# SCH_Rubik_2_2024-01-29.net
KiCad netlist of a schematic drawn in EasyEDA
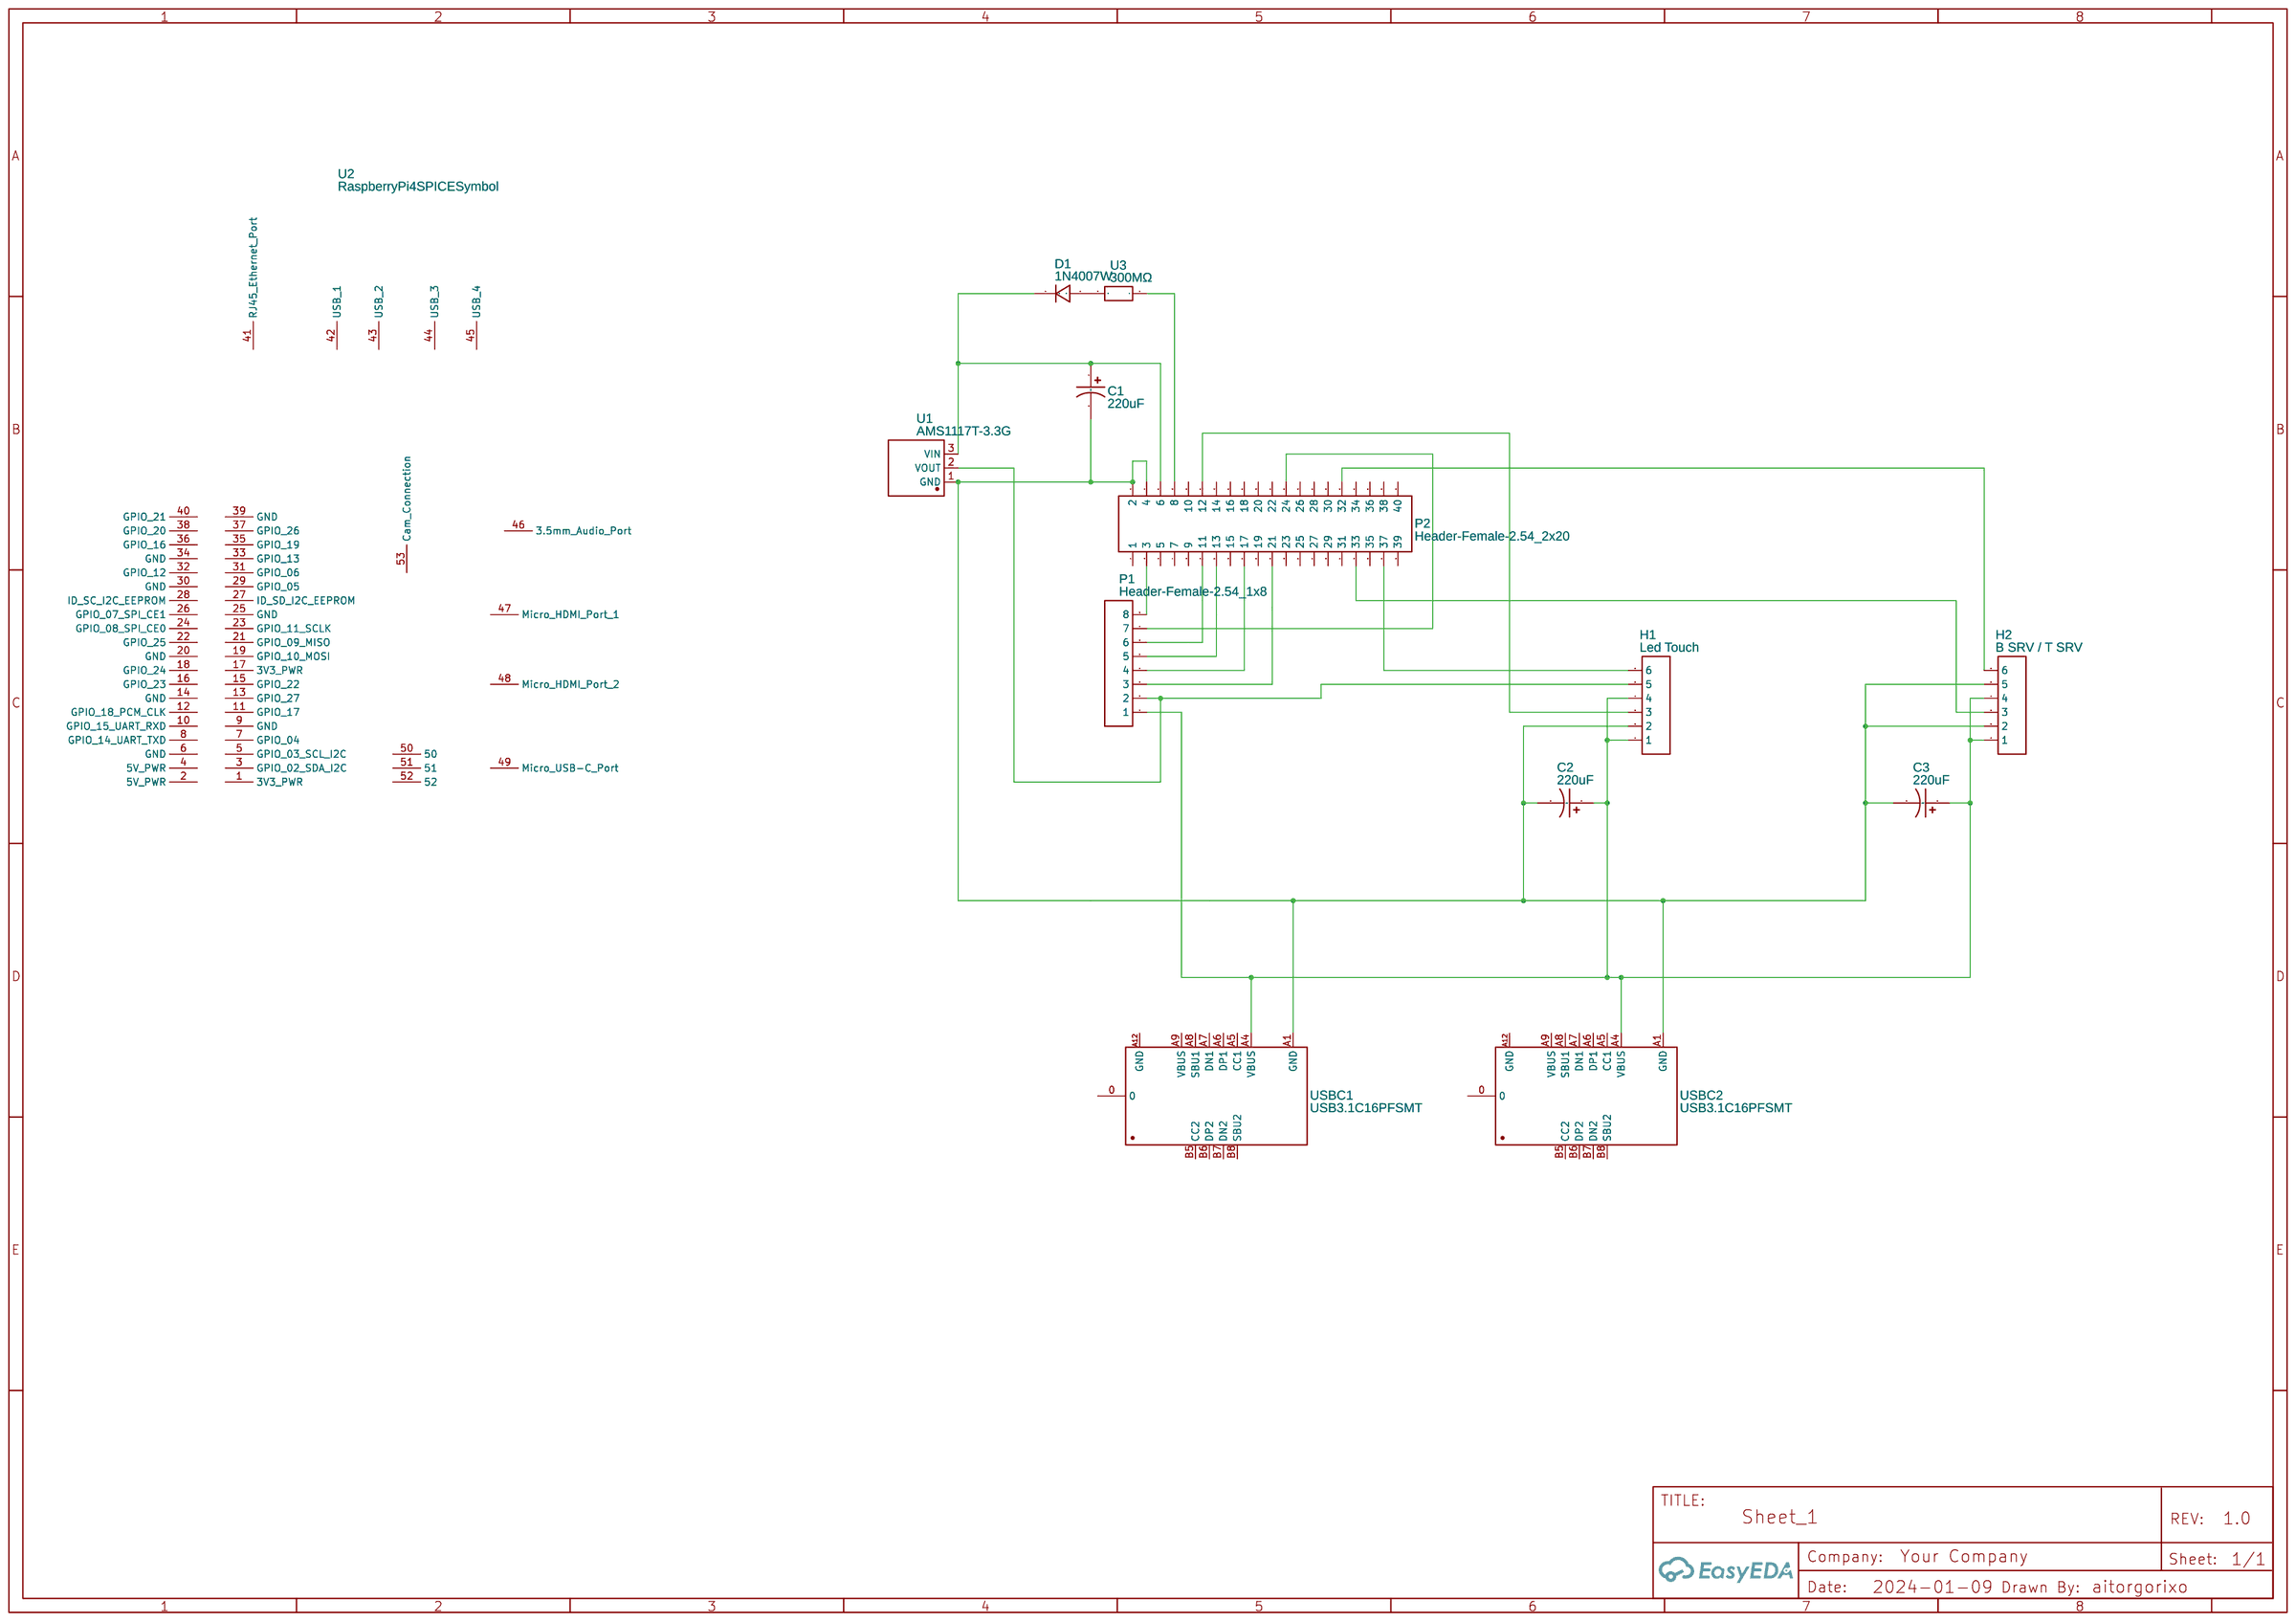
[diagram p0: schematic sheet]

(export (version "E")
  (design (tool "Eeschema 10.0.6"))
  (components
    (comp (ref "C1")
      (value "220uF")
      (fields
        (field (name "Manufacturer Part") "35YXG220MLLCT78X16")
        (field (name "Manufacturer") "rubycon(红宝石)")
      )
      (libsource (lib "") (part "35YXG220MLLCT78X16_1"))
    )
    (comp (ref "C2")
      (value "220uF")
      (fields
        (field (name "Manufacturer Part") "35YXG220MLLCT78X16")
        (field (name "Manufacturer") "rubycon(红宝石)")
      )
      (libsource (lib "") (part "35YXG220MLLCT78X16"))
    )
    (comp (ref "C3")
      (value "220uF")
      (fields
        (field (name "Manufacturer Part") "35YXG220MLLCT78X16")
        (field (name "Manufacturer") "rubycon(红宝石)")
      )
      (libsource (lib "") (part "35YXG220MLLCT78X16"))
    )
    (comp (ref "D1")
      (value "1N4007W")
      (fields (field (name "Manufacturer") "BLUE ROCKET"))
      (libsource (lib "") (part "1N4007W"))
    )
    (comp (ref "H1")
      (value "Led Touch")
      (fields (field (name "Manufacturer Part") "2.54-1x6P直针") (field (name "Manufacturer") "BOOMELE(博穆精密)"))
      (libsource (lib "") (part "Header-Male-2.54_1x6"))
    )
    (comp (ref "H2")
      (value "B SRV / T SRV")
      (fields (field (name "Manufacturer Part") "2.54-1x6P直针") (field (name "Manufacturer") "BOOMELE(博穆精密)"))
      (libsource (lib "") (part "Header-Male-2.54_1x6"))
    )
    (comp (ref "P1")
      (value "Header-Female-2.54_1x8")
      (fields (field (name "Manufacturer Part") "2.54-1*8P母环保") (field (name "Manufacturer") "BOOMELE(博穆精密)"))
      (libsource (lib "") (part "Header-Female-2.54_1x8"))
    )
    (comp (ref "P2")
      (value "Header-Female-2.54_2x20")
      (fields (field (name "Manufacturer Part") "2.54-2*20P母") (field (name "Manufacturer") "BOOMELE(博穆精密)"))
      (libsource (lib "") (part "Header-Female-2.54_2x20"))
    )
    (comp (ref "U1")
      (value "AMS1117T-3.3G")
      (fields (field (name "Manufacturer") "HGC(深圳汉芯)"))
      (libsource (lib "") (part "AMS1117T-3.3G"))
    )
    (comp (ref "U2") (value "RaspberryPi4SPICESymbol") (libsource (lib "") (part "RaspberryPi4SPICESymbol")))
    (comp (ref "U3")
      (value "300MΩ")
      (fields
        (field (name "Manufacturer Part") "WW12JTR300")
        (field (name "Manufacturer") "SEI(Stackpole Electronics Inc.)")
      )
      (libsource (lib "") (part "WW12JTR300"))
    )
    (comp (ref "USBC1")
      (value "USB3.1C16PFSMT")
      (fields (field (name "Manufacturer Part") "918-418K2023S40001") (field (name "Manufacturer") "精拓金"))
      (libsource (lib "") (part "USB3.1C16PFSMT"))
    )
    (comp (ref "USBC2")
      (value "USB3.1C16PFSMT")
      (fields (field (name "Manufacturer Part") "918-418K2023S40001") (field (name "Manufacturer") "精拓金"))
      (libsource (lib "") (part "USB3.1C16PFSMT"))
    )
  )
  (nets
    (net (code "1") (name "Net-(C2-Pad1)") (class "Default")
      (node (ref "C2") (pin "1") (pinfunction "1_1") (pintype "unspecified"))
      (node (ref "C3") (pin "1") (pinfunction "1_1") (pintype "unspecified"))
      (node (ref "H1") (pin "1") (pinfunction "1_1") (pintype "input"))
      (node (ref "H1") (pin "4") (pinfunction "4_4") (pintype "input"))
      (node (ref "H2") (pin "1") (pinfunction "1_1") (pintype "input"))
      (node (ref "H2") (pin "4") (pinfunction "4_4") (pintype "input"))
      (node (ref "P1") (pin "1") (pinfunction "1_1") (pintype "input"))
      (node (ref "USBC1") (pin "A4") (pinfunction "VBUS_A4") (pintype "unspecified"))
      (node (ref "USBC2") (pin "A4") (pinfunction "VBUS_A4") (pintype "unspecified"))
    )
    (net (code "2") (name "Net-(D1-Pad2)") (class "Default")
      (node (ref "D1") (pin "2") (pinfunction "2_2") (pintype "unspecified"))
      (node (ref "U3") (pin "2") (pinfunction "2_2") (pintype "unspecified"))
    )
    (net (code "3") (name "Net-(H1-Pad3)") (class "Default")
      (node (ref "H1") (pin "3") (pinfunction "3_3") (pintype "input"))
      (node (ref "P2") (pin "12") (pinfunction "12_12") (pintype "input"))
    )
    (net (code "4") (name "Net-(H1-Pad6)") (class "Default")
      (node (ref "H1") (pin "6") (pinfunction "6_6") (pintype "input"))
      (node (ref "P2") (pin "37") (pinfunction "37_37") (pintype "input"))
    )
    (net (code "5") (name "Net-(H2-Pad3)") (class "Default")
      (node (ref "H2") (pin "3") (pinfunction "3_3") (pintype "input"))
      (node (ref "P2") (pin "33") (pinfunction "33_33") (pintype "input"))
    )
    (net (code "6") (name "Net-(H2-Pad6)") (class "Default")
      (node (ref "H2") (pin "6") (pinfunction "6_6") (pintype "input"))
      (node (ref "P2") (pin "32") (pinfunction "32_32") (pintype "input"))
    )
    (net (code "7") (name "Net-(P1-Pad3)") (class "Default")
      (node (ref "P1") (pin "3") (pinfunction "3_3") (pintype "input"))
      (node (ref "P2") (pin "21") (pinfunction "21_21") (pintype "input"))
    )
    (net (code "8") (name "Net-(P1-Pad4)") (class "Default")
      (node (ref "P1") (pin "4") (pinfunction "4_4") (pintype "input"))
      (node (ref "P2") (pin "17") (pinfunction "17_17") (pintype "input"))
    )
    (net (code "9") (name "Net-(P1-Pad5)") (class "Default")
      (node (ref "P1") (pin "5") (pinfunction "5_5") (pintype "input"))
      (node (ref "P2") (pin "13") (pinfunction "13_13") (pintype "input"))
    )
    (net (code "10") (name "Net-(P1-Pad6)") (class "Default")
      (node (ref "P1") (pin "6") (pinfunction "6_6") (pintype "input"))
      (node (ref "P2") (pin "11") (pinfunction "11_11") (pintype "input"))
    )
    (net (code "11") (name "Net-(P1-Pad7)") (class "Default")
      (node (ref "P1") (pin "7") (pinfunction "7_7") (pintype "input"))
      (node (ref "P2") (pin "24") (pinfunction "24_24") (pintype "input"))
    )
    (net (code "12") (name "Net-(P1-Pad8)") (class "Default")
      (node (ref "P1") (pin "8") (pinfunction "8_8") (pintype "input"))
      (node (ref "P2") (pin "3") (pinfunction "3_3") (pintype "input"))
    )
    (net (code "13") (name "Net-(P2-Pad8)") (class "Default")
      (node (ref "P2") (pin "8") (pinfunction "8_8") (pintype "input"))
      (node (ref "U3") (pin "1") (pinfunction "1_1") (pintype "unspecified"))
    )
    (net (code "14") (name "Net-(U1-GND)") (class "Default")
      (node (ref "C1") (pin "2") (pinfunction "2_2") (pintype "unspecified"))
      (node (ref "C2") (pin "2") (pinfunction "2_2") (pintype "unspecified"))
      (node (ref "C3") (pin "2") (pinfunction "2_2") (pintype "unspecified"))
      (node (ref "H1") (pin "2") (pinfunction "2_2") (pintype "input"))
      (node (ref "H2") (pin "2") (pinfunction "2_2") (pintype "input"))
      (node (ref "H2") (pin "5") (pinfunction "5_5") (pintype "input"))
      (node (ref "P2") (pin "2") (pinfunction "2_2") (pintype "input"))
      (node (ref "P2") (pin "4") (pinfunction "4_4") (pintype "input"))
      (node (ref "U1") (pin "1") (pinfunction "GND_1") (pintype "unspecified"))
      (node (ref "USBC1") (pin "A1") (pinfunction "GND_A1") (pintype "unspecified"))
      (node (ref "USBC2") (pin "A1") (pinfunction "GND_A1") (pintype "unspecified"))
    )
    (net (code "15") (name "Net-(U1-VIN)") (class "Default")
      (node (ref "C1") (pin "1") (pinfunction "1_1") (pintype "unspecified"))
      (node (ref "D1") (pin "1") (pinfunction "1_1") (pintype "unspecified"))
      (node (ref "P2") (pin "6") (pinfunction "6_6") (pintype "input"))
      (node (ref "U1") (pin "3") (pinfunction "VIN_3") (pintype "unspecified"))
    )
    (net (code "16") (name "Net-(U1-VOUT)") (class "Default")
      (node (ref "H1") (pin "5") (pinfunction "5_5") (pintype "input"))
      (node (ref "P1") (pin "2") (pinfunction "2_2") (pintype "input"))
      (node (ref "U1") (pin "2") (pinfunction "VOUT_2") (pintype "unspecified"))
    )
    (net (code "17") (name "unconnected-(P2-Pad1)") (class "Default")
      (node (ref "P2") (pin "1") (pinfunction "1_1") (pintype "input"))
    )
    (net (code "18") (name "unconnected-(P2-Pad5)") (class "Default")
      (node (ref "P2") (pin "5") (pinfunction "5_5") (pintype "input"))
    )
    (net (code "19") (name "unconnected-(P2-Pad7)") (class "Default")
      (node (ref "P2") (pin "7") (pinfunction "7_7") (pintype "input"))
    )
    (net (code "20") (name "unconnected-(P2-Pad9)") (class "Default")
      (node (ref "P2") (pin "9") (pinfunction "9_9") (pintype "input"))
    )
    (net (code "21") (name "unconnected-(P2-Pad10)") (class "Default")
      (node (ref "P2") (pin "10") (pinfunction "10_10") (pintype "input"))
    )
    (net (code "22") (name "unconnected-(P2-Pad14)") (class "Default")
      (node (ref "P2") (pin "14") (pinfunction "14_14") (pintype "input"))
    )
    (net (code "23") (name "unconnected-(P2-Pad15)") (class "Default")
      (node (ref "P2") (pin "15") (pinfunction "15_15") (pintype "input"))
    )
    (net (code "24") (name "unconnected-(P2-Pad16)") (class "Default")
      (node (ref "P2") (pin "16") (pinfunction "16_16") (pintype "input"))
    )
    (net (code "25") (name "unconnected-(P2-Pad18)") (class "Default")
      (node (ref "P2") (pin "18") (pinfunction "18_18") (pintype "input"))
    )
    (net (code "26") (name "unconnected-(P2-Pad19)") (class "Default")
      (node (ref "P2") (pin "19") (pinfunction "19_19") (pintype "input"))
    )
    (net (code "27") (name "unconnected-(P2-Pad20)") (class "Default")
      (node (ref "P2") (pin "20") (pinfunction "20_20") (pintype "input"))
    )
    (net (code "28") (name "unconnected-(P2-Pad22)") (class "Default")
      (node (ref "P2") (pin "22") (pinfunction "22_22") (pintype "input"))
    )
    (net (code "29") (name "unconnected-(P2-Pad23)") (class "Default")
      (node (ref "P2") (pin "23") (pinfunction "23_23") (pintype "input"))
    )
    (net (code "30") (name "unconnected-(P2-Pad25)") (class "Default")
      (node (ref "P2") (pin "25") (pinfunction "25_25") (pintype "input"))
    )
    (net (code "31") (name "unconnected-(P2-Pad26)") (class "Default")
      (node (ref "P2") (pin "26") (pinfunction "26_26") (pintype "input"))
    )
    (net (code "32") (name "unconnected-(P2-Pad27)") (class "Default")
      (node (ref "P2") (pin "27") (pinfunction "27_27") (pintype "input"))
    )
    (net (code "33") (name "unconnected-(P2-Pad28)") (class "Default")
      (node (ref "P2") (pin "28") (pinfunction "28_28") (pintype "input"))
    )
    (net (code "34") (name "unconnected-(P2-Pad29)") (class "Default")
      (node (ref "P2") (pin "29") (pinfunction "29_29") (pintype "input"))
    )
    (net (code "35") (name "unconnected-(P2-Pad30)") (class "Default")
      (node (ref "P2") (pin "30") (pinfunction "30_30") (pintype "input"))
    )
    (net (code "36") (name "unconnected-(P2-Pad31)") (class "Default")
      (node (ref "P2") (pin "31") (pinfunction "31_31") (pintype "input"))
    )
    (net (code "37") (name "unconnected-(P2-Pad34)") (class "Default")
      (node (ref "P2") (pin "34") (pinfunction "34_34") (pintype "input"))
    )
    (net (code "38") (name "unconnected-(P2-Pad35)") (class "Default")
      (node (ref "P2") (pin "35") (pinfunction "35_35") (pintype "input"))
    )
    (net (code "39") (name "unconnected-(P2-Pad36)") (class "Default")
      (node (ref "P2") (pin "36") (pinfunction "36_36") (pintype "input"))
    )
    (net (code "40") (name "unconnected-(P2-Pad38)") (class "Default")
      (node (ref "P2") (pin "38") (pinfunction "38_38") (pintype "input"))
    )
    (net (code "41") (name "unconnected-(P2-Pad39)") (class "Default")
      (node (ref "P2") (pin "39") (pinfunction "39_39") (pintype "input"))
    )
    (net (code "42") (name "unconnected-(P2-Pad40)") (class "Default")
      (node (ref "P2") (pin "40") (pinfunction "40_40") (pintype "input"))
    )
    (net (code "43") (name "unconnected-(U2-3.5mm_Audio_Port-Pad46)") (class "Default")
      (node (ref "U2") (pin "46") (pinfunction "3.5mm_Audio_Port_46") (pintype "unspecified"))
    )
    (net (code "44") (name "unconnected-(U2-3V3_PWR-Pad1)") (class "Default")
      (node (ref "U2") (pin "1") (pinfunction "3V3_PWR_1") (pintype "unspecified"))
    )
    (net (code "45") (name "unconnected-(U2-3V3_PWR-Pad17)") (class "Default")
      (node (ref "U2") (pin "17") (pinfunction "3V3_PWR_17") (pintype "unspecified"))
    )
    (net (code "46") (name "unconnected-(U2-5V_PWR-Pad2)") (class "Default")
      (node (ref "U2") (pin "2") (pinfunction "5V_PWR_2") (pintype "unspecified"))
    )
    (net (code "47") (name "unconnected-(U2-5V_PWR-Pad4)") (class "Default")
      (node (ref "U2") (pin "4") (pinfunction "5V_PWR_4") (pintype "unspecified"))
    )
    (net (code "48") (name "unconnected-(U2-Cam_Connection-Pad53)") (class "Default")
      (node (ref "U2") (pin "53") (pinfunction "Cam_Connection_53") (pintype "unspecified"))
    )
    (net (code "49") (name "unconnected-(U2-GND-Pad6)") (class "Default")
      (node (ref "U2") (pin "6") (pinfunction "GND_6") (pintype "unspecified"))
    )
    (net (code "50") (name "unconnected-(U2-GND-Pad9)") (class "Default")
      (node (ref "U2") (pin "9") (pinfunction "GND_9") (pintype "unspecified"))
    )
    (net (code "51") (name "unconnected-(U2-GND-Pad14)") (class "Default")
      (node (ref "U2") (pin "14") (pinfunction "GND_14") (pintype "unspecified"))
    )
    (net (code "52") (name "unconnected-(U2-GND-Pad20)") (class "Default")
      (node (ref "U2") (pin "20") (pinfunction "GND_20") (pintype "unspecified"))
    )
    (net (code "53") (name "unconnected-(U2-GND-Pad25)") (class "Default")
      (node (ref "U2") (pin "25") (pinfunction "GND_25") (pintype "unspecified"))
    )
    (net (code "54") (name "unconnected-(U2-GND-Pad30)") (class "Default")
      (node (ref "U2") (pin "30") (pinfunction "GND_30") (pintype "unspecified"))
    )
    (net (code "55") (name "unconnected-(U2-GND-Pad34)") (class "Default")
      (node (ref "U2") (pin "34") (pinfunction "GND_34") (pintype "unspecified"))
    )
    (net (code "56") (name "unconnected-(U2-GND-Pad39)") (class "Default")
      (node (ref "U2") (pin "39") (pinfunction "GND_39") (pintype "unspecified"))
    )
    (net (code "57") (name "unconnected-(U2-GPIO_02_SDA_I2C-Pad3)") (class "Default")
      (node (ref "U2") (pin "3") (pinfunction "GPIO_02_SDA_I2C_3") (pintype "unspecified"))
    )
    (net (code "58") (name "unconnected-(U2-GPIO_03_SCL_I2C-Pad5)") (class "Default")
      (node (ref "U2") (pin "5") (pinfunction "GPIO_03_SCL_I2C_5") (pintype "unspecified"))
    )
    (net (code "59") (name "unconnected-(U2-GPIO_04-Pad7)") (class "Default")
      (node (ref "U2") (pin "7") (pinfunction "GPIO_04_7") (pintype "unspecified"))
    )
    (net (code "60") (name "unconnected-(U2-GPIO_05-Pad29)") (class "Default")
      (node (ref "U2") (pin "29") (pinfunction "GPIO_05_29") (pintype "unspecified"))
    )
    (net (code "61") (name "unconnected-(U2-GPIO_06-Pad31)") (class "Default")
      (node (ref "U2") (pin "31") (pinfunction "GPIO_06_31") (pintype "unspecified"))
    )
    (net (code "62") (name "unconnected-(U2-GPIO_07_SPI_CE1-Pad26)") (class "Default")
      (node (ref "U2") (pin "26") (pinfunction "GPIO_07_SPI_CE1_26") (pintype "unspecified"))
    )
    (net (code "63") (name "unconnected-(U2-GPIO_08_SPI_CE0-Pad24)") (class "Default")
      (node (ref "U2") (pin "24") (pinfunction "GPIO_08_SPI_CE0_24") (pintype "unspecified"))
    )
    (net (code "64") (name "unconnected-(U2-GPIO_09_MISO-Pad21)") (class "Default")
      (node (ref "U2") (pin "21") (pinfunction "GPIO_09_MISO_21") (pintype "unspecified"))
    )
    (net (code "65") (name "unconnected-(U2-GPIO_10_MOSI-Pad19)") (class "Default")
      (node (ref "U2") (pin "19") (pinfunction "GPIO_10_MOSI_19") (pintype "unspecified"))
    )
    (net (code "66") (name "unconnected-(U2-GPIO_11_SCLK-Pad23)") (class "Default")
      (node (ref "U2") (pin "23") (pinfunction "GPIO_11_SCLK_23") (pintype "unspecified"))
    )
    (net (code "67") (name "unconnected-(U2-GPIO_12-Pad32)") (class "Default")
      (node (ref "U2") (pin "32") (pinfunction "GPIO_12_32") (pintype "unspecified"))
    )
    (net (code "68") (name "unconnected-(U2-GPIO_13-Pad33)") (class "Default")
      (node (ref "U2") (pin "33") (pinfunction "GPIO_13_33") (pintype "unspecified"))
    )
    (net (code "69") (name "unconnected-(U2-GPIO_14_UART_TXD-Pad8)") (class "Default")
      (node (ref "U2") (pin "8") (pinfunction "GPIO_14_UART_TXD_8") (pintype "unspecified"))
    )
    (net (code "70") (name "unconnected-(U2-GPIO_15_UART_RXD-Pad10)") (class "Default")
      (node (ref "U2") (pin "10") (pinfunction "GPIO_15_UART_RXD_10") (pintype "unspecified"))
    )
    (net (code "71") (name "unconnected-(U2-GPIO_16-Pad36)") (class "Default")
      (node (ref "U2") (pin "36") (pinfunction "GPIO_16_36") (pintype "unspecified"))
    )
    (net (code "72") (name "unconnected-(U2-GPIO_17-Pad11)") (class "Default")
      (node (ref "U2") (pin "11") (pinfunction "GPIO_17_11") (pintype "unspecified"))
    )
    (net (code "73") (name "unconnected-(U2-GPIO_18_PCM_CLK-Pad12)") (class "Default")
      (node (ref "U2") (pin "12") (pinfunction "GPIO_18_PCM_CLK_12") (pintype "unspecified"))
    )
    (net (code "74") (name "unconnected-(U2-GPIO_19-Pad35)") (class "Default")
      (node (ref "U2") (pin "35") (pinfunction "GPIO_19_35") (pintype "unspecified"))
    )
    (net (code "75") (name "unconnected-(U2-GPIO_20-Pad38)") (class "Default")
      (node (ref "U2") (pin "38") (pinfunction "GPIO_20_38") (pintype "unspecified"))
    )
    (net (code "76") (name "unconnected-(U2-GPIO_21-Pad40)") (class "Default")
      (node (ref "U2") (pin "40") (pinfunction "GPIO_21_40") (pintype "unspecified"))
    )
    (net (code "77") (name "unconnected-(U2-GPIO_22-Pad15)") (class "Default")
      (node (ref "U2") (pin "15") (pinfunction "GPIO_22_15") (pintype "unspecified"))
    )
    (net (code "78") (name "unconnected-(U2-GPIO_23-Pad16)") (class "Default")
      (node (ref "U2") (pin "16") (pinfunction "GPIO_23_16") (pintype "unspecified"))
    )
    (net (code "79") (name "unconnected-(U2-GPIO_24-Pad18)") (class "Default")
      (node (ref "U2") (pin "18") (pinfunction "GPIO_24_18") (pintype "unspecified"))
    )
    (net (code "80") (name "unconnected-(U2-GPIO_25-Pad22)") (class "Default")
      (node (ref "U2") (pin "22") (pinfunction "GPIO_25_22") (pintype "unspecified"))
    )
    (net (code "81") (name "unconnected-(U2-GPIO_26-Pad37)") (class "Default")
      (node (ref "U2") (pin "37") (pinfunction "GPIO_26_37") (pintype "unspecified"))
    )
    (net (code "82") (name "unconnected-(U2-GPIO_27-Pad13)") (class "Default")
      (node (ref "U2") (pin "13") (pinfunction "GPIO_27_13") (pintype "unspecified"))
    )
    (net (code "83") (name "unconnected-(U2-ID_SC_I2C_EEPROM-Pad28)") (class "Default")
      (node (ref "U2") (pin "28") (pinfunction "ID_SC_I2C_EEPROM_28") (pintype "unspecified"))
    )
    (net (code "84") (name "unconnected-(U2-ID_SD_I2C_EEPROM-Pad27)") (class "Default")
      (node (ref "U2") (pin "27") (pinfunction "ID_SD_I2C_EEPROM_27") (pintype "unspecified"))
    )
    (net (code "85") (name "unconnected-(U2-Micro_HDMI_Port_1-Pad47)") (class "Default")
      (node (ref "U2") (pin "47") (pinfunction "Micro_HDMI_Port_1_47") (pintype "unspecified"))
    )
    (net (code "86") (name "unconnected-(U2-Micro_HDMI_Port_2-Pad48)") (class "Default")
      (node (ref "U2") (pin "48") (pinfunction "Micro_HDMI_Port_2_48") (pintype "unspecified"))
    )
    (net (code "87") (name "unconnected-(U2-Micro_USB-C_Port-Pad49)") (class "Default")
      (node (ref "U2") (pin "49") (pinfunction "Micro_USB-C_Port_49") (pintype "unspecified"))
    )
    (net (code "88") (name "unconnected-(U2-Pad50)") (class "Default")
      (node (ref "U2") (pin "50") (pinfunction "50_50") (pintype "unspecified"))
    )
    (net (code "89") (name "unconnected-(U2-Pad51)") (class "Default")
      (node (ref "U2") (pin "51") (pinfunction "51_51") (pintype "unspecified"))
    )
    (net (code "90") (name "unconnected-(U2-Pad52)") (class "Default")
      (node (ref "U2") (pin "52") (pinfunction "52_52") (pintype "unspecified"))
    )
    (net (code "91") (name "unconnected-(U2-RJ45_Ethernet_Port-Pad41)") (class "Default")
      (node (ref "U2") (pin "41") (pinfunction "RJ45_Ethernet_Port_41") (pintype "unspecified"))
    )
    (net (code "92") (name "unconnected-(U2-USB_1-Pad42)") (class "Default")
      (node (ref "U2") (pin "42") (pinfunction "USB_1_42") (pintype "unspecified"))
    )
    (net (code "93") (name "unconnected-(U2-USB_2-Pad43)") (class "Default")
      (node (ref "U2") (pin "43") (pinfunction "USB_2_43") (pintype "unspecified"))
    )
    (net (code "94") (name "unconnected-(U2-USB_3-Pad44)") (class "Default")
      (node (ref "U2") (pin "44") (pinfunction "USB_3_44") (pintype "unspecified"))
    )
    (net (code "95") (name "unconnected-(U2-USB_4-Pad45)") (class "Default")
      (node (ref "U2") (pin "45") (pinfunction "USB_4_45") (pintype "unspecified"))
    )
    (net (code "96") (name "unconnected-(USBC1-CC1-PadA5)") (class "Default")
      (node (ref "USBC1") (pin "A5") (pinfunction "CC1_A5") (pintype "unspecified"))
    )
    (net (code "97") (name "unconnected-(USBC1-CC2-PadB5)") (class "Default")
      (node (ref "USBC1") (pin "B5") (pinfunction "CC2_B5") (pintype "unspecified"))
    )
    (net (code "98") (name "unconnected-(USBC1-DN1-PadA7)") (class "Default")
      (node (ref "USBC1") (pin "A7") (pinfunction "DN1_A7") (pintype "unspecified"))
    )
    (net (code "99") (name "unconnected-(USBC1-DN2-PadB7)") (class "Default")
      (node (ref "USBC1") (pin "B7") (pinfunction "DN2_B7") (pintype "unspecified"))
    )
    (net (code "100") (name "unconnected-(USBC1-DP1-PadA6)") (class "Default")
      (node (ref "USBC1") (pin "A6") (pinfunction "DP1_A6") (pintype "unspecified"))
    )
    (net (code "101") (name "unconnected-(USBC1-DP2-PadB6)") (class "Default")
      (node (ref "USBC1") (pin "B6") (pinfunction "DP2_B6") (pintype "unspecified"))
    )
    (net (code "102") (name "unconnected-(USBC1-GND-PadA12)") (class "Default")
      (node (ref "USBC1") (pin "A12") (pinfunction "GND_A12") (pintype "unspecified"))
    )
    (net (code "103") (name "unconnected-(USBC1-Pad0)") (class "Default")
      (node (ref "USBC1") (pin "0") (pinfunction "0_0") (pintype "unspecified"))
    )
    (net (code "104") (name "unconnected-(USBC1-SBU1-PadA8)") (class "Default")
      (node (ref "USBC1") (pin "A8") (pinfunction "SBU1_A8") (pintype "unspecified"))
    )
    (net (code "105") (name "unconnected-(USBC1-SBU2-PadB8)") (class "Default")
      (node (ref "USBC1") (pin "B8") (pinfunction "SBU2_B8") (pintype "unspecified"))
    )
    (net (code "106") (name "unconnected-(USBC1-VBUS-PadA9)") (class "Default")
      (node (ref "USBC1") (pin "A9") (pinfunction "VBUS_A9") (pintype "unspecified"))
    )
    (net (code "107") (name "unconnected-(USBC2-CC1-PadA5)") (class "Default")
      (node (ref "USBC2") (pin "A5") (pinfunction "CC1_A5") (pintype "unspecified"))
    )
    (net (code "108") (name "unconnected-(USBC2-CC2-PadB5)") (class "Default")
      (node (ref "USBC2") (pin "B5") (pinfunction "CC2_B5") (pintype "unspecified"))
    )
    (net (code "109") (name "unconnected-(USBC2-DN1-PadA7)") (class "Default")
      (node (ref "USBC2") (pin "A7") (pinfunction "DN1_A7") (pintype "unspecified"))
    )
    (net (code "110") (name "unconnected-(USBC2-DN2-PadB7)") (class "Default")
      (node (ref "USBC2") (pin "B7") (pinfunction "DN2_B7") (pintype "unspecified"))
    )
    (net (code "111") (name "unconnected-(USBC2-DP1-PadA6)") (class "Default")
      (node (ref "USBC2") (pin "A6") (pinfunction "DP1_A6") (pintype "unspecified"))
    )
    (net (code "112") (name "unconnected-(USBC2-DP2-PadB6)") (class "Default")
      (node (ref "USBC2") (pin "B6") (pinfunction "DP2_B6") (pintype "unspecified"))
    )
    (net (code "113") (name "unconnected-(USBC2-GND-PadA12)") (class "Default")
      (node (ref "USBC2") (pin "A12") (pinfunction "GND_A12") (pintype "unspecified"))
    )
    (net (code "114") (name "unconnected-(USBC2-Pad0)") (class "Default")
      (node (ref "USBC2") (pin "0") (pinfunction "0_0") (pintype "unspecified"))
    )
    (net (code "115") (name "unconnected-(USBC2-SBU1-PadA8)") (class "Default")
      (node (ref "USBC2") (pin "A8") (pinfunction "SBU1_A8") (pintype "unspecified"))
    )
    (net (code "116") (name "unconnected-(USBC2-SBU2-PadB8)") (class "Default")
      (node (ref "USBC2") (pin "B8") (pinfunction "SBU2_B8") (pintype "unspecified"))
    )
    (net (code "117") (name "unconnected-(USBC2-VBUS-PadA9)") (class "Default")
      (node (ref "USBC2") (pin "A9") (pinfunction "VBUS_A9") (pintype "unspecified"))
    )
  )
)
